# VocaTap-_rev_1_0.net
KiCad netlist of a schematic drawn in EasyEDA
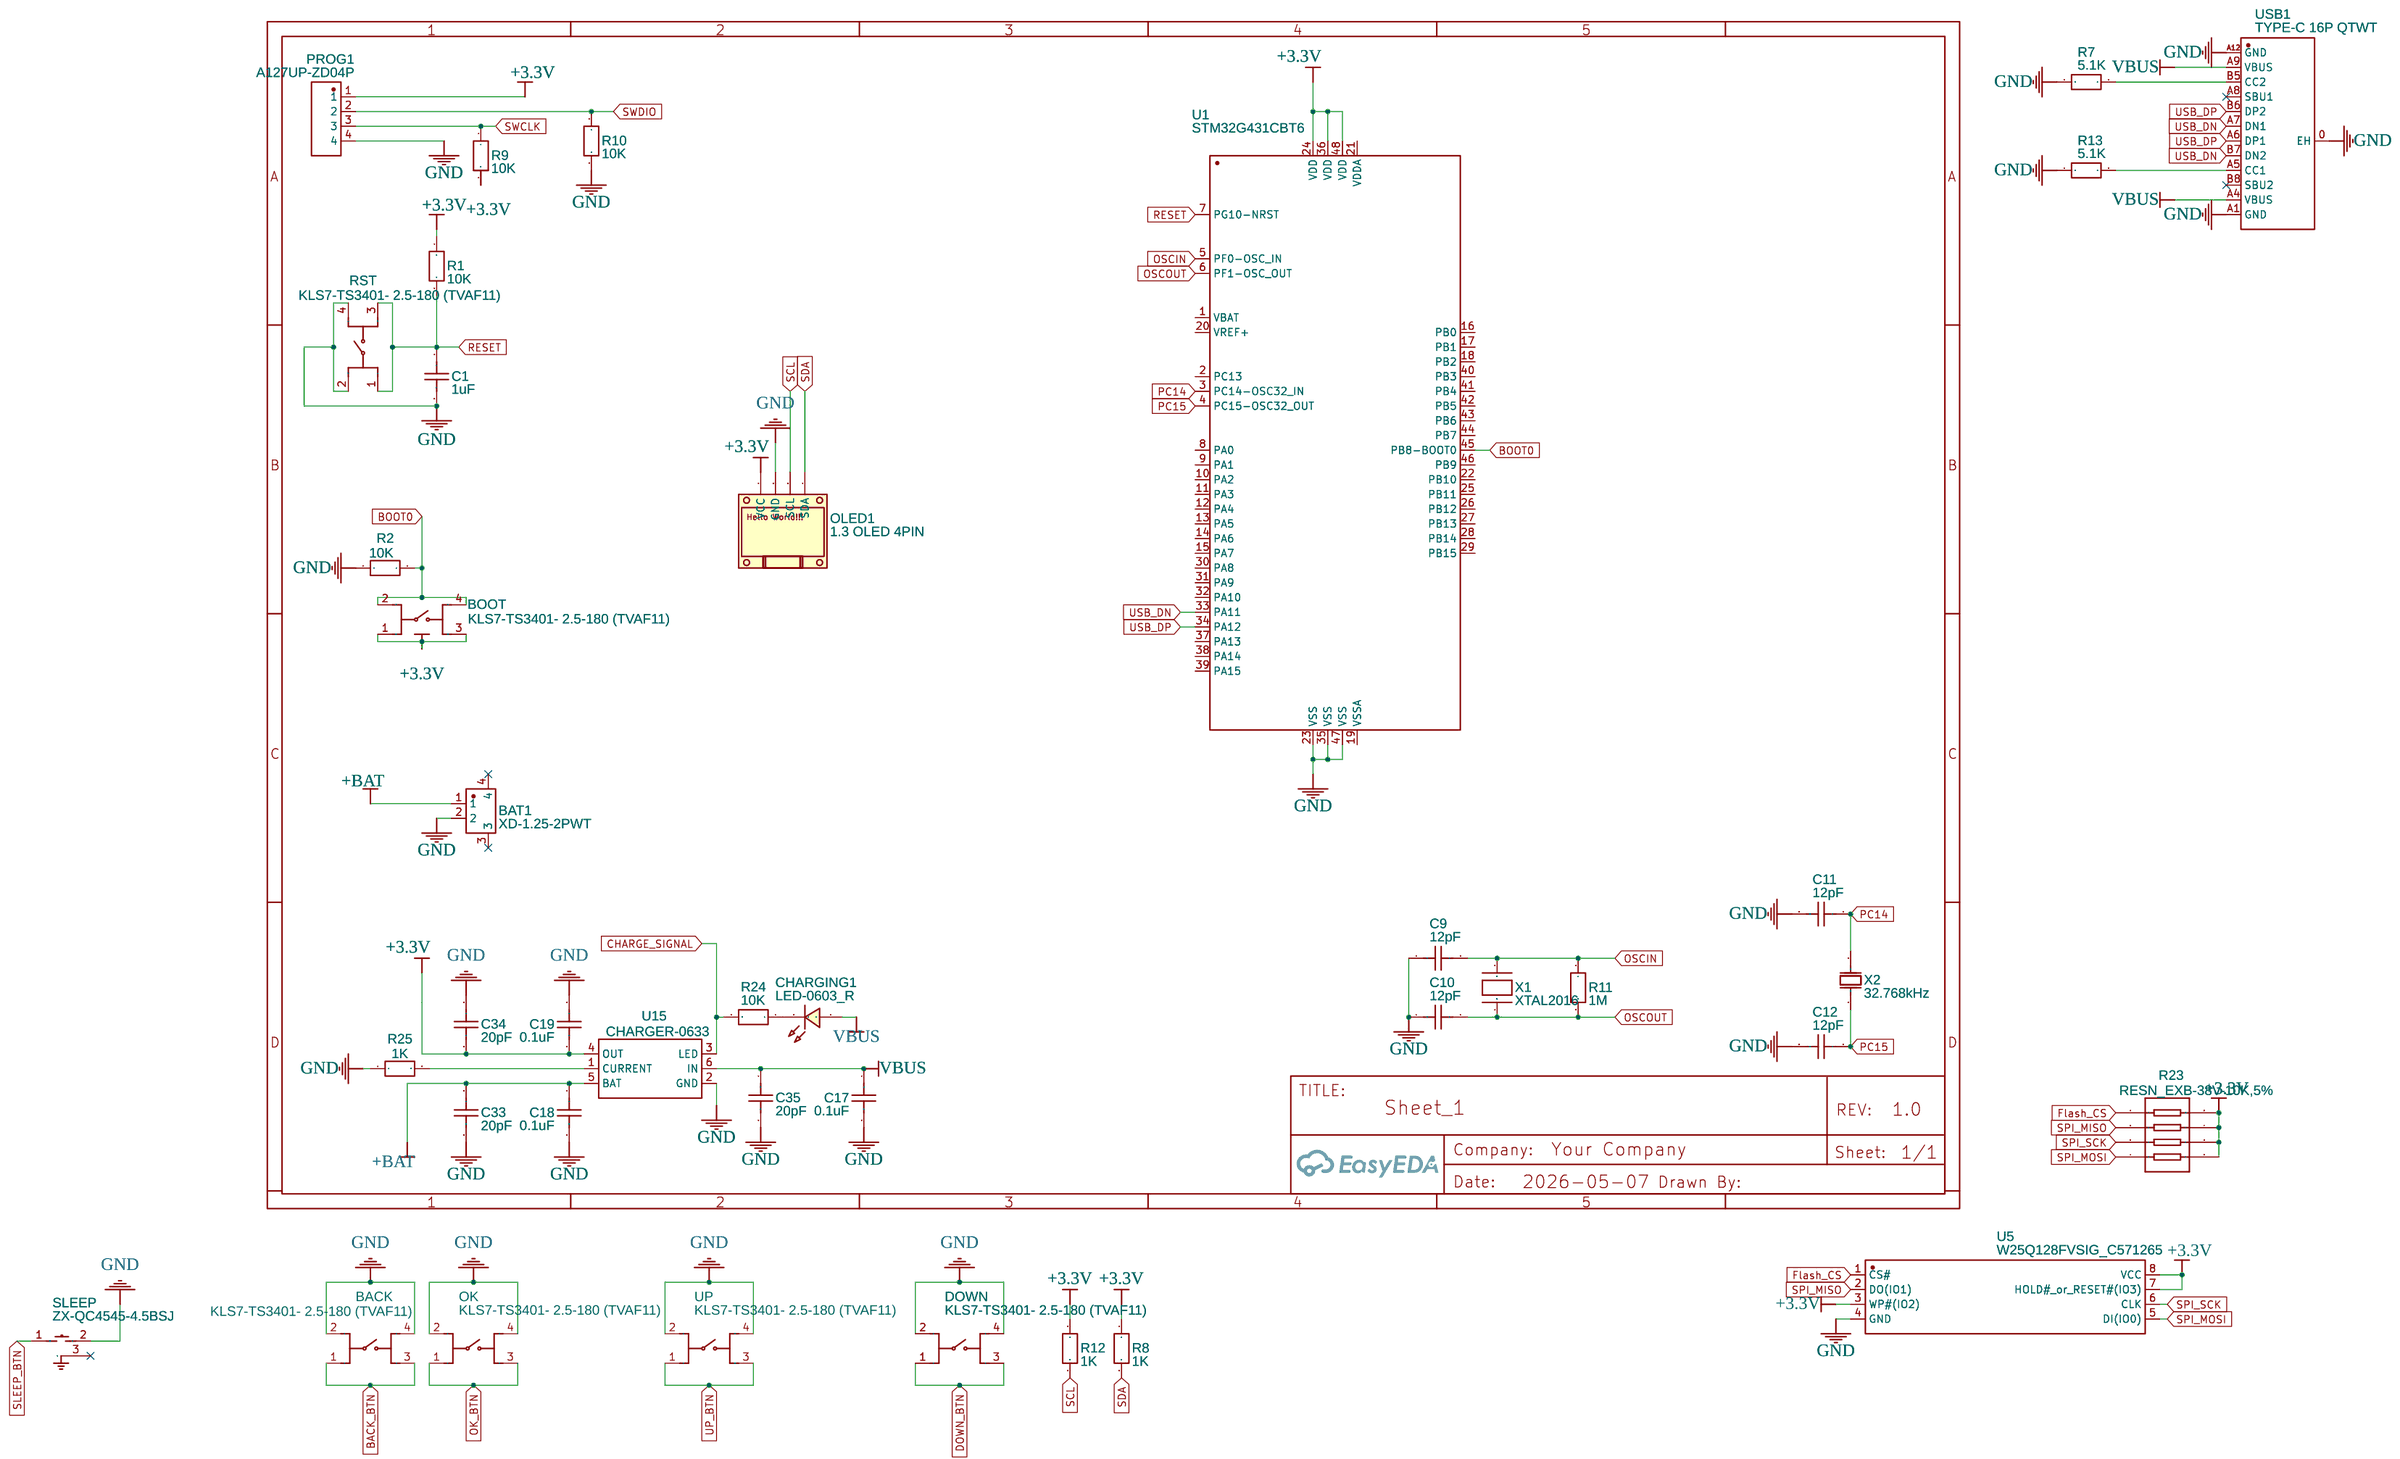
[diagram p0: schematic sheet]

(export (version "E")
  (design (tool "Eeschema 10.0.6"))
  (components
    (comp (ref "BACK")
      (value "KLS7-TS3401- 2.5-180 (TVAF11)")
      (libsource (lib "") (part "KLS7-TS3401- 2.5-180 (TVAF11)_2"))
    )
    (comp (ref "BAT1")
      (value "XD-1.25-2PWT")
      (fields (field (name "Manufacturer") "XUNDA(讯答)"))
      (libsource (lib "") (part "XD-1.25-2PWT"))
    )
    (comp (ref "BOOT")
      (value "KLS7-TS3401- 2.5-180 (TVAF11)")
      (libsource (lib "") (part "KLS7-TS3401- 2.5-180 (TVAF11)_3"))
    )
    (comp (ref "C1") (value "1uF") (libsource (lib "") (part "C_0603_US_2")))
    (comp (ref "C9") (value "12pF") (libsource (lib "") (part "C_0603_US_1")))
    (comp (ref "C10") (value "12pF") (libsource (lib "") (part "C_0603_US_1")))
    (comp (ref "C11") (value "12pF") (libsource (lib "") (part "C_0603_US_1")))
    (comp (ref "C12") (value "12pF") (libsource (lib "") (part "C_0603_US_1")))
    (comp (ref "C17") (value "0.1uF") (libsource (lib "") (part "C_0603_US")))
    (comp (ref "C18") (value "0.1uF") (libsource (lib "") (part "C_0603_US")))
    (comp (ref "C19") (value "0.1uF") (libsource (lib "") (part "C_0603_US")))
    (comp (ref "C33") (value "20pF") (libsource (lib "") (part "C_0603_US_2")))
    (comp (ref "C34") (value "20pF") (libsource (lib "") (part "C_0603_US_2")))
    (comp (ref "C35") (value "20pF") (libsource (lib "") (part "C_0603_US_2")))
    (comp (ref "CHARGING1")
      (value "LED-0603_R")
      (fields
        (field (name "Manufacturer Part") "19-217/R6C-AL1M2VY/3T")
        (field (name "Manufacturer") "EVERLIGHT(台湾亿光)")
      )
      (libsource (lib "") (part "LED-0603_R"))
    )
    (comp (ref "DOWN")
      (value "KLS7-TS3401- 2.5-180 (TVAF11)")
      (libsource (lib "") (part "KLS7-TS3401- 2.5-180 (TVAF11)_1"))
    )
    (comp (ref "OK")
      (value "KLS7-TS3401- 2.5-180 (TVAF11)")
      (libsource (lib "") (part "KLS7-TS3401- 2.5-180 (TVAF11)_5"))
    )
    (comp (ref "OLED1") (value "1.3 OLED 4PIN") (libsource (lib "") (part "1.3 OLED 4PIN")))
    (comp (ref "PROG1")
      (value "A127UP-ZD04P")
      (fields (field (name "Manufacturer") "BXCONN(宝讯)"))
      (libsource (lib "") (part "A127UP-ZD04P"))
    )
    (comp (ref "R1") (value "10K") (libsource (lib "") (part "R_0603_EU_1")))
    (comp (ref "R2") (value "10K") (libsource (lib "") (part "R_0603_EU")))
    (comp (ref "R7") (value "5.1K") (libsource (lib "") (part "R_0603_EU")))
    (comp (ref "R8") (value "1K") (libsource (lib "") (part "R_0603_EU_1")))
    (comp (ref "R9") (value "10K") (libsource (lib "") (part "R_0603_EU_1")))
    (comp (ref "R10") (value "10K") (libsource (lib "") (part "R_0603_EU_1")))
    (comp (ref "R11") (value "1M") (libsource (lib "") (part "R_0603_EU_1")))
    (comp (ref "R12") (value "1K") (libsource (lib "") (part "R_0603_EU_1")))
    (comp (ref "R13") (value "5.1K") (libsource (lib "") (part "R_0603_EU")))
    (comp (ref "R23")
      (value "RESN_EXB-38V-10K,5%")
      (fields (field (name "Manufacturer Part") "RESN_EXB-38V-22R,5%"))
      (libsource (lib "") (part "RESN_EXB-38V-22R,5%"))
    )
    (comp (ref "R24") (value "10K") (libsource (lib "") (part "R_0603_EU_2")))
    (comp (ref "R25") (value "1K") (libsource (lib "") (part "R_0603_EU")))
    (comp (ref "RST")
      (value "KLS7-TS3401- 2.5-180 (TVAF11)")
      (libsource (lib "") (part "KLS7-TS3401- 2.5-180 (TVAF11)"))
    )
    (comp (ref "SLEEP")
      (value "ZX-QC4545-4.5BSJ")
      (fields (field (name "Manufacturer") "Megastar(兆星)"))
      (libsource (lib "") (part "ZX-QC4545-4.5BSJ"))
    )
    (comp (ref "U1")
      (value "STM32G431CBT6")
      (fields (field (name "Manufacturer") "ST(意法半导体)"))
      (libsource (lib "") (part "STM32G431CBT6"))
    )
    (comp (ref "U5")
      (value "W25Q128FVSIG_C571265")
      (fields (field (name "Manufacturer Part") "W25Q128FVSIG") (field (name "Manufacturer") "WINBOND(华邦)"))
      (libsource (lib "") (part "W25Q128FVSIG_C571265"))
    )
    (comp (ref "U15")
      (value "CHARGER-0633")
      (fields
        (field (name "Manufacturer Part") "TP4067-3.70V-SOT26-R")
        (field (name "Manufacturer") "TOPPOWER(南京拓微)")
      )
      (libsource (lib "") (part "TP4067-3.70V-SOT26-R"))
    )
    (comp (ref "UP")
      (value "KLS7-TS3401- 2.5-180 (TVAF11)")
      (libsource (lib "") (part "KLS7-TS3401- 2.5-180 (TVAF11)_4"))
    )
    (comp (ref "USB1")
      (value "TYPE-C 16P QTWT")
      (fields (field (name "Manufacturer") "SHOU HAN(首韩)"))
      (libsource (lib "") (part "TYPE-C 16P QTWT"))
    )
    (comp (ref "X1") (value "XTAL2016") (libsource (lib "") (part "XTAL2016")))
    (comp (ref "X2")
      (value "32.768kHz")
      (fields
        (field (name "Manufacturer Part") "NX3215SA-32.768K-STD-MUA-8")
        (field (name "Manufacturer") "NDK")
      )
      (libsource (lib "") (part "NX3215SA-32.768KHZ(STD-MUA-8)"))
    )
  )
  (nets
    (net (code "1") (name "+3.3V") (class "Default")
      (node (ref "BOOT") (pin "1") (pinfunction "1_1") (pintype "unspecified"))
      (node (ref "BOOT") (pin "3") (pinfunction "3_3") (pintype "unspecified"))
      (node (ref "C19") (pin "2") (pinfunction "2_2") (pintype "unspecified"))
      (node (ref "C34") (pin "2") (pinfunction "2_2") (pintype "unspecified"))
      (node (ref "OLED1") (pin "1") (pinfunction "VCC_1") (pintype "unspecified"))
      (node (ref "PROG1") (pin "1") (pinfunction "1_1") (pintype "unspecified"))
      (node (ref "R1") (pin "1") (pinfunction "1_1") (pintype "unspecified"))
      (node (ref "R12") (pin "1") (pinfunction "1_1") (pintype "unspecified"))
      (node (ref "R23") (pin "5") (pinfunction "5_5") (pintype "input"))
      (node (ref "R23") (pin "6") (pinfunction "6_6") (pintype "input"))
      (node (ref "R23") (pin "7") (pinfunction "7_7") (pintype "input"))
      (node (ref "R23") (pin "8") (pinfunction "8_8") (pintype "input"))
      (node (ref "R8") (pin "1") (pinfunction "1_1") (pintype "unspecified"))
      (node (ref "R9") (pin "2") (pinfunction "2_2") (pintype "unspecified"))
      (node (ref "U1") (pin "24") (pinfunction "VDD_24") (pintype "unspecified"))
      (node (ref "U1") (pin "36") (pinfunction "VDD_36") (pintype "unspecified"))
      (node (ref "U1") (pin "48") (pinfunction "VDD_48") (pintype "unspecified"))
      (node (ref "U15") (pin "4") (pinfunction "OUT_4") (pintype "unspecified"))
      (node (ref "U5") (pin "3") (pinfunction "WP#(IO2)_3") (pintype "unspecified"))
      (node (ref "U5") (pin "7") (pinfunction "HOLD#_or_RESET#(IO3)_7") (pintype "unspecified"))
      (node (ref "U5") (pin "8") (pinfunction "VCC_8") (pintype "unspecified"))
    )
    (net (code "2") (name "+BAT") (class "Default")
      (node (ref "BAT1") (pin "1") (pinfunction "1_1") (pintype "unspecified"))
      (node (ref "C18") (pin "1") (pinfunction "1_1") (pintype "unspecified"))
      (node (ref "C33") (pin "1") (pinfunction "1_1") (pintype "unspecified"))
      (node (ref "U15") (pin "5") (pinfunction "BAT_5") (pintype "unspecified"))
    )
    (net (code "3") (name "BACK_BTN") (class "Default")
      (node (ref "BACK") (pin "1") (pinfunction "1_1") (pintype "unspecified"))
      (node (ref "BACK") (pin "3") (pinfunction "3_3") (pintype "unspecified"))
    )
    (net (code "4") (name "BOOT0") (class "Default")
      (node (ref "BOOT") (pin "2") (pinfunction "2_2") (pintype "unspecified"))
      (node (ref "BOOT") (pin "4") (pinfunction "4_4") (pintype "unspecified"))
      (node (ref "R2") (pin "2") (pinfunction "2_2") (pintype "unspecified"))
      (node (ref "U1") (pin "45") (pinfunction "PB8-BOOT0_45") (pintype "unspecified"))
    )
    (net (code "5") (name "CHARGE_SIGNAL") (class "Default")
      (node (ref "R24") (pin "2") (pinfunction "2_2") (pintype "unspecified"))
      (node (ref "U15") (pin "3") (pinfunction "LED_3") (pintype "unspecified"))
    )
    (net (code "6") (name "DOWN_BTN") (class "Default")
      (node (ref "DOWN") (pin "1") (pinfunction "1_1") (pintype "unspecified"))
      (node (ref "DOWN") (pin "3") (pinfunction "3_3") (pintype "unspecified"))
    )
    (net (code "7") (name "Flash_CS") (class "Default")
      (node (ref "R23") (pin "1") (pinfunction "1_1") (pintype "input"))
      (node (ref "U5") (pin "1") (pinfunction "CS#_1") (pintype "unspecified"))
    )
    (net (code "8") (name "GND") (class "Default")
      (node (ref "BACK") (pin "2") (pinfunction "2_2") (pintype "unspecified"))
      (node (ref "BACK") (pin "4") (pinfunction "4_4") (pintype "unspecified"))
      (node (ref "BAT1") (pin "2") (pinfunction "2_2") (pintype "unspecified"))
      (node (ref "C1") (pin "2") (pinfunction "2_2") (pintype "unspecified"))
      (node (ref "C10") (pin "1") (pinfunction "1_1") (pintype "unspecified"))
      (node (ref "C11") (pin "1") (pinfunction "1_1") (pintype "unspecified"))
      (node (ref "C12") (pin "1") (pinfunction "1_1") (pintype "unspecified"))
      (node (ref "C17") (pin "2") (pinfunction "2_2") (pintype "unspecified"))
      (node (ref "C18") (pin "2") (pinfunction "2_2") (pintype "unspecified"))
      (node (ref "C19") (pin "1") (pinfunction "1_1") (pintype "unspecified"))
      (node (ref "C33") (pin "2") (pinfunction "2_2") (pintype "unspecified"))
      (node (ref "C34") (pin "1") (pinfunction "1_1") (pintype "unspecified"))
      (node (ref "C35") (pin "2") (pinfunction "2_2") (pintype "unspecified"))
      (node (ref "C9") (pin "1") (pinfunction "1_1") (pintype "unspecified"))
      (node (ref "DOWN") (pin "2") (pinfunction "2_2") (pintype "unspecified"))
      (node (ref "DOWN") (pin "4") (pinfunction "4_4") (pintype "unspecified"))
      (node (ref "OK") (pin "2") (pinfunction "2_2") (pintype "unspecified"))
      (node (ref "OK") (pin "4") (pinfunction "4_4") (pintype "unspecified"))
      (node (ref "OLED1") (pin "2") (pinfunction "GND_2") (pintype "unspecified"))
      (node (ref "PROG1") (pin "4") (pinfunction "4_4") (pintype "unspecified"))
      (node (ref "R10") (pin "2") (pinfunction "2_2") (pintype "unspecified"))
      (node (ref "R13") (pin "1") (pinfunction "1_1") (pintype "unspecified"))
      (node (ref "R2") (pin "1") (pinfunction "1_1") (pintype "unspecified"))
      (node (ref "R25") (pin "1") (pinfunction "1_1") (pintype "unspecified"))
      (node (ref "R7") (pin "1") (pinfunction "1_1") (pintype "unspecified"))
      (node (ref "RST") (pin "2") (pinfunction "2_2") (pintype "unspecified"))
      (node (ref "RST") (pin "4") (pinfunction "4_4") (pintype "unspecified"))
      (node (ref "SLEEP") (pin "2") (pinfunction "2_2") (pintype "unspecified"))
      (node (ref "U1") (pin "23") (pinfunction "VSS_23") (pintype "unspecified"))
      (node (ref "U1") (pin "35") (pinfunction "VSS_35") (pintype "unspecified"))
      (node (ref "U1") (pin "47") (pinfunction "VSS_47") (pintype "unspecified"))
      (node (ref "U15") (pin "2") (pinfunction "GND_2") (pintype "unspecified"))
      (node (ref "U5") (pin "4") (pinfunction "GND_4") (pintype "unspecified"))
      (node (ref "UP") (pin "2") (pinfunction "2_2") (pintype "unspecified"))
      (node (ref "UP") (pin "4") (pinfunction "4_4") (pintype "unspecified"))
      (node (ref "USB1") (pin "0") (pinfunction "EH_0") (pintype "unspecified"))
      (node (ref "USB1") (pin "A1") (pinfunction "GND_A1") (pintype "unspecified"))
      (node (ref "USB1") (pin "A12") (pinfunction "GND_A12") (pintype "unspecified"))
    )
    (net (code "9") (name "Net-(CHARGING1-Pad2)") (class "Default")
      (node (ref "CHARGING1") (pin "2") (pinfunction "2_2") (pintype "unspecified"))
      (node (ref "R24") (pin "1") (pinfunction "1_1") (pintype "unspecified"))
    )
    (net (code "10") (name "Net-(U15-CURRENT)") (class "Default")
      (node (ref "R25") (pin "2") (pinfunction "2_2") (pintype "unspecified"))
      (node (ref "U15") (pin "1") (pinfunction "CURRENT_1") (pintype "unspecified"))
    )
    (net (code "11") (name "Net-(USB1-CC1)") (class "Default")
      (node (ref "R13") (pin "2") (pinfunction "2_2") (pintype "unspecified"))
      (node (ref "USB1") (pin "A5") (pinfunction "CC1_A5") (pintype "unspecified"))
    )
    (net (code "12") (name "Net-(USB1-CC2)") (class "Default")
      (node (ref "R7") (pin "2") (pinfunction "2_2") (pintype "unspecified"))
      (node (ref "USB1") (pin "B5") (pinfunction "CC2_B5") (pintype "unspecified"))
    )
    (net (code "13") (name "OK_BTN") (class "Default")
      (node (ref "OK") (pin "1") (pinfunction "1_1") (pintype "unspecified"))
      (node (ref "OK") (pin "3") (pinfunction "3_3") (pintype "unspecified"))
    )
    (net (code "14") (name "OSCIN") (class "Default")
      (node (ref "C9") (pin "2") (pinfunction "2_2") (pintype "unspecified"))
      (node (ref "R11") (pin "1") (pinfunction "1_1") (pintype "unspecified"))
      (node (ref "U1") (pin "5") (pinfunction "PF0-OSC_IN_5") (pintype "unspecified"))
      (node (ref "X1") (pin "1") (pinfunction "P$1_1") (pintype "bidirectional"))
    )
    (net (code "15") (name "OSCOUT") (class "Default")
      (node (ref "C10") (pin "2") (pinfunction "2_2") (pintype "unspecified"))
      (node (ref "R11") (pin "2") (pinfunction "2_2") (pintype "unspecified"))
      (node (ref "U1") (pin "6") (pinfunction "PF1-OSC_OUT_6") (pintype "unspecified"))
      (node (ref "X1") (pin "3") (pinfunction "P$2_3") (pintype "bidirectional"))
    )
    (net (code "16") (name "PC14") (class "Default")
      (node (ref "C11") (pin "2") (pinfunction "2_2") (pintype "unspecified"))
      (node (ref "U1") (pin "3") (pinfunction "PC14-OSC32_IN_3") (pintype "unspecified"))
      (node (ref "X2") (pin "1") (pinfunction "OSC1_1") (pintype "input"))
    )
    (net (code "17") (name "PC15") (class "Default")
      (node (ref "C12") (pin "2") (pinfunction "2_2") (pintype "unspecified"))
      (node (ref "U1") (pin "4") (pinfunction "PC15-OSC32_OUT_4") (pintype "unspecified"))
      (node (ref "X2") (pin "2") (pinfunction "OSC2_2") (pintype "input"))
    )
    (net (code "18") (name "RESET") (class "Default")
      (node (ref "C1") (pin "1") (pinfunction "1_1") (pintype "unspecified"))
      (node (ref "R1") (pin "2") (pinfunction "2_2") (pintype "unspecified"))
      (node (ref "RST") (pin "1") (pinfunction "1_1") (pintype "unspecified"))
      (node (ref "RST") (pin "3") (pinfunction "3_3") (pintype "unspecified"))
      (node (ref "U1") (pin "7") (pinfunction "PG10-NRST_7") (pintype "unspecified"))
    )
    (net (code "19") (name "SCL") (class "Default")
      (node (ref "OLED1") (pin "3") (pinfunction "SCL_3") (pintype "unspecified"))
      (node (ref "R12") (pin "2") (pinfunction "2_2") (pintype "unspecified"))
    )
    (net (code "20") (name "SDA") (class "Default")
      (node (ref "OLED1") (pin "4") (pinfunction "SDA_4") (pintype "unspecified"))
      (node (ref "R8") (pin "2") (pinfunction "2_2") (pintype "unspecified"))
    )
    (net (code "21") (name "SLEEP_BTN") (class "Default")
      (node (ref "SLEEP") (pin "1") (pinfunction "1_1") (pintype "unspecified"))
    )
    (net (code "22") (name "SPI_MISO") (class "Default")
      (node (ref "R23") (pin "2") (pinfunction "2_2") (pintype "input"))
      (node (ref "U5") (pin "2") (pinfunction "DO(IO1)_2") (pintype "unspecified"))
    )
    (net (code "23") (name "SPI_MOSI") (class "Default")
      (node (ref "R23") (pin "4") (pinfunction "4_4") (pintype "input"))
      (node (ref "U5") (pin "5") (pinfunction "DI(IO0)_5") (pintype "unspecified"))
    )
    (net (code "24") (name "SPI_SCK") (class "Default")
      (node (ref "R23") (pin "3") (pinfunction "3_3") (pintype "input"))
      (node (ref "U5") (pin "6") (pinfunction "CLK_6") (pintype "unspecified"))
    )
    (net (code "25") (name "SWCLK") (class "Default")
      (node (ref "PROG1") (pin "3") (pinfunction "3_3") (pintype "unspecified"))
      (node (ref "R9") (pin "1") (pinfunction "1_1") (pintype "unspecified"))
    )
    (net (code "26") (name "SWDIO") (class "Default")
      (node (ref "PROG1") (pin "2") (pinfunction "2_2") (pintype "unspecified"))
      (node (ref "R10") (pin "1") (pinfunction "1_1") (pintype "unspecified"))
    )
    (net (code "27") (name "UP_BTN") (class "Default")
      (node (ref "UP") (pin "1") (pinfunction "1_1") (pintype "unspecified"))
      (node (ref "UP") (pin "3") (pinfunction "3_3") (pintype "unspecified"))
    )
    (net (code "28") (name "USB_DN") (class "Default")
      (node (ref "U1") (pin "33") (pinfunction "PA11_33") (pintype "unspecified"))
      (node (ref "USB1") (pin "A7") (pinfunction "DN1_A7") (pintype "unspecified"))
      (node (ref "USB1") (pin "B7") (pinfunction "DN2_B7") (pintype "unspecified"))
    )
    (net (code "29") (name "USB_DP") (class "Default")
      (node (ref "U1") (pin "34") (pinfunction "PA12_34") (pintype "unspecified"))
      (node (ref "USB1") (pin "A6") (pinfunction "DP1_A6") (pintype "unspecified"))
      (node (ref "USB1") (pin "B6") (pinfunction "DP2_B6") (pintype "unspecified"))
    )
    (net (code "30") (name "VBUS") (class "Default")
      (node (ref "C17") (pin "1") (pinfunction "1_1") (pintype "unspecified"))
      (node (ref "C35") (pin "1") (pinfunction "1_1") (pintype "unspecified"))
      (node (ref "CHARGING1") (pin "1") (pinfunction "1_1") (pintype "unspecified"))
      (node (ref "U15") (pin "6") (pinfunction "IN_6") (pintype "unspecified"))
      (node (ref "USB1") (pin "A4") (pinfunction "VBUS_A4") (pintype "unspecified"))
      (node (ref "USB1") (pin "A9") (pinfunction "VBUS_A9") (pintype "unspecified"))
    )
    (net (code "31") (name "unconnected-(BAT1-Pad3)") (class "Default")
      (node (ref "BAT1") (pin "3") (pinfunction "3_3") (pintype "unspecified+no_connect"))
    )
    (net (code "32") (name "unconnected-(BAT1-Pad4)") (class "Default")
      (node (ref "BAT1") (pin "4") (pinfunction "4_4") (pintype "unspecified+no_connect"))
    )
    (net (code "33") (name "unconnected-(SLEEP-Pad3)") (class "Default")
      (node (ref "SLEEP") (pin "3") (pinfunction "3_3") (pintype "unspecified+no_connect"))
    )
    (net (code "34") (name "unconnected-(U1-PA0-Pad8)") (class "Default")
      (node (ref "U1") (pin "8") (pinfunction "PA0_8") (pintype "unspecified"))
    )
    (net (code "35") (name "unconnected-(U1-PA1-Pad9)") (class "Default")
      (node (ref "U1") (pin "9") (pinfunction "PA1_9") (pintype "unspecified"))
    )
    (net (code "36") (name "unconnected-(U1-PA2-Pad10)") (class "Default")
      (node (ref "U1") (pin "10") (pinfunction "PA2_10") (pintype "unspecified"))
    )
    (net (code "37") (name "unconnected-(U1-PA3-Pad11)") (class "Default")
      (node (ref "U1") (pin "11") (pinfunction "PA3_11") (pintype "unspecified"))
    )
    (net (code "38") (name "unconnected-(U1-PA4-Pad12)") (class "Default")
      (node (ref "U1") (pin "12") (pinfunction "PA4_12") (pintype "unspecified"))
    )
    (net (code "39") (name "unconnected-(U1-PA5-Pad13)") (class "Default")
      (node (ref "U1") (pin "13") (pinfunction "PA5_13") (pintype "unspecified"))
    )
    (net (code "40") (name "unconnected-(U1-PA6-Pad14)") (class "Default")
      (node (ref "U1") (pin "14") (pinfunction "PA6_14") (pintype "unspecified"))
    )
    (net (code "41") (name "unconnected-(U1-PA7-Pad15)") (class "Default")
      (node (ref "U1") (pin "15") (pinfunction "PA7_15") (pintype "unspecified"))
    )
    (net (code "42") (name "unconnected-(U1-PA8-Pad30)") (class "Default")
      (node (ref "U1") (pin "30") (pinfunction "PA8_30") (pintype "unspecified"))
    )
    (net (code "43") (name "unconnected-(U1-PA9-Pad31)") (class "Default")
      (node (ref "U1") (pin "31") (pinfunction "PA9_31") (pintype "unspecified"))
    )
    (net (code "44") (name "unconnected-(U1-PA10-Pad32)") (class "Default")
      (node (ref "U1") (pin "32") (pinfunction "PA10_32") (pintype "unspecified"))
    )
    (net (code "45") (name "unconnected-(U1-PA13-Pad37)") (class "Default")
      (node (ref "U1") (pin "37") (pinfunction "PA13_37") (pintype "unspecified"))
    )
    (net (code "46") (name "unconnected-(U1-PA14-Pad38)") (class "Default")
      (node (ref "U1") (pin "38") (pinfunction "PA14_38") (pintype "unspecified"))
    )
    (net (code "47") (name "unconnected-(U1-PA15-Pad39)") (class "Default")
      (node (ref "U1") (pin "39") (pinfunction "PA15_39") (pintype "unspecified"))
    )
    (net (code "48") (name "unconnected-(U1-PB0-Pad16)") (class "Default")
      (node (ref "U1") (pin "16") (pinfunction "PB0_16") (pintype "unspecified"))
    )
    (net (code "49") (name "unconnected-(U1-PB1-Pad17)") (class "Default")
      (node (ref "U1") (pin "17") (pinfunction "PB1_17") (pintype "unspecified"))
    )
    (net (code "50") (name "unconnected-(U1-PB2-Pad18)") (class "Default")
      (node (ref "U1") (pin "18") (pinfunction "PB2_18") (pintype "unspecified"))
    )
    (net (code "51") (name "unconnected-(U1-PB3-Pad40)") (class "Default")
      (node (ref "U1") (pin "40") (pinfunction "PB3_40") (pintype "unspecified"))
    )
    (net (code "52") (name "unconnected-(U1-PB4-Pad41)") (class "Default")
      (node (ref "U1") (pin "41") (pinfunction "PB4_41") (pintype "unspecified"))
    )
    (net (code "53") (name "unconnected-(U1-PB5-Pad42)") (class "Default")
      (node (ref "U1") (pin "42") (pinfunction "PB5_42") (pintype "unspecified"))
    )
    (net (code "54") (name "unconnected-(U1-PB6-Pad43)") (class "Default")
      (node (ref "U1") (pin "43") (pinfunction "PB6_43") (pintype "unspecified"))
    )
    (net (code "55") (name "unconnected-(U1-PB7-Pad44)") (class "Default")
      (node (ref "U1") (pin "44") (pinfunction "PB7_44") (pintype "unspecified"))
    )
    (net (code "56") (name "unconnected-(U1-PB9-Pad46)") (class "Default")
      (node (ref "U1") (pin "46") (pinfunction "PB9_46") (pintype "unspecified"))
    )
    (net (code "57") (name "unconnected-(U1-PB10-Pad22)") (class "Default")
      (node (ref "U1") (pin "22") (pinfunction "PB10_22") (pintype "unspecified"))
    )
    (net (code "58") (name "unconnected-(U1-PB11-Pad25)") (class "Default")
      (node (ref "U1") (pin "25") (pinfunction "PB11_25") (pintype "unspecified"))
    )
    (net (code "59") (name "unconnected-(U1-PB12-Pad26)") (class "Default")
      (node (ref "U1") (pin "26") (pinfunction "PB12_26") (pintype "unspecified"))
    )
    (net (code "60") (name "unconnected-(U1-PB13-Pad27)") (class "Default")
      (node (ref "U1") (pin "27") (pinfunction "PB13_27") (pintype "unspecified"))
    )
    (net (code "61") (name "unconnected-(U1-PB14-Pad28)") (class "Default")
      (node (ref "U1") (pin "28") (pinfunction "PB14_28") (pintype "unspecified"))
    )
    (net (code "62") (name "unconnected-(U1-PB15-Pad29)") (class "Default")
      (node (ref "U1") (pin "29") (pinfunction "PB15_29") (pintype "unspecified"))
    )
    (net (code "63") (name "unconnected-(U1-PC13-Pad2)") (class "Default")
      (node (ref "U1") (pin "2") (pinfunction "PC13_2") (pintype "unspecified"))
    )
    (net (code "64") (name "unconnected-(U1-VBAT-Pad1)") (class "Default")
      (node (ref "U1") (pin "1") (pinfunction "VBAT_1") (pintype "unspecified"))
    )
    (net (code "65") (name "unconnected-(U1-VDDA-Pad21)") (class "Default")
      (node (ref "U1") (pin "21") (pinfunction "VDDA_21") (pintype "unspecified"))
    )
    (net (code "66") (name "unconnected-(U1-VREF+-Pad20)") (class "Default")
      (node (ref "U1") (pin "20") (pinfunction "VREF+_20") (pintype "unspecified"))
    )
    (net (code "67") (name "unconnected-(U1-VSSA-Pad19)") (class "Default")
      (node (ref "U1") (pin "19") (pinfunction "VSSA_19") (pintype "unspecified"))
    )
    (net (code "68") (name "unconnected-(USB1-SBU1-PadA8)") (class "Default")
      (node (ref "USB1") (pin "A8") (pinfunction "SBU1_A8") (pintype "unspecified+no_connect"))
    )
    (net (code "69") (name "unconnected-(USB1-SBU2-PadB8)") (class "Default")
      (node (ref "USB1") (pin "B8") (pinfunction "SBU2_B8") (pintype "unspecified+no_connect"))
    )
  )
)
